# fabflash-mk-2-driver.net
KiCad netlist of a schematic drawn in EAGLE
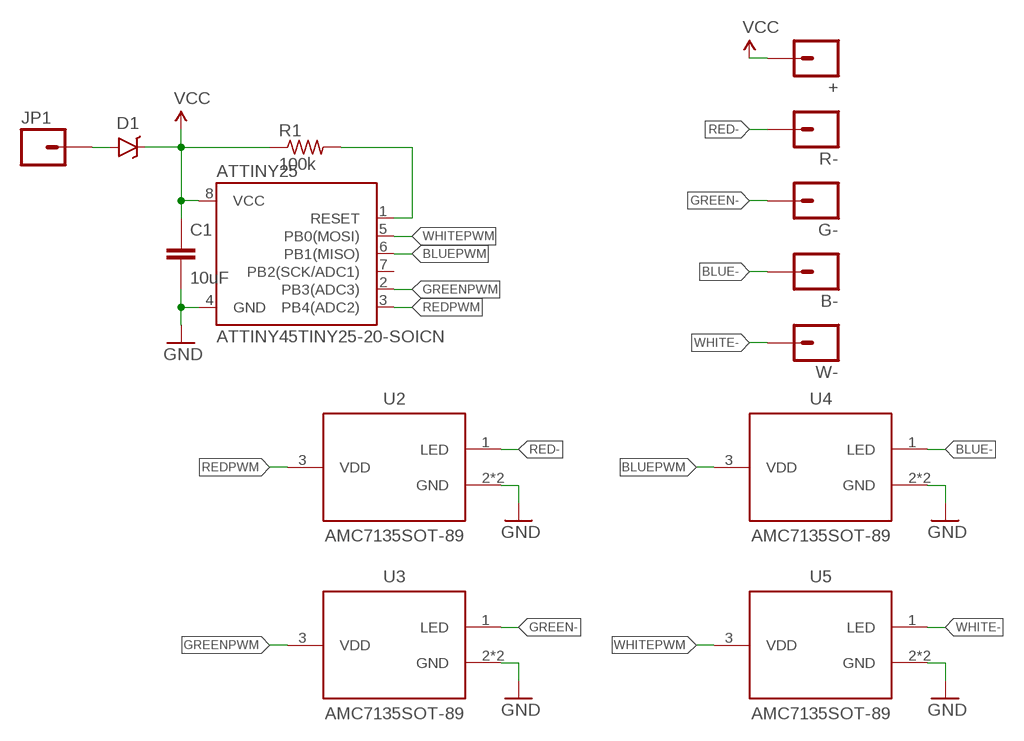
[diagram p0: schematic, sheet 1]

(export (version "E")
  (design (tool "Eeschema 10.0.6"))
  (components
    (comp (ref "+")
      (value "M01PTH-0.9MM")
      (footprint "eagle-import:1X01-0.9MM-NS")
      (libsource (lib "eagle-import") (part "M01PTH-0.9MM"))
    )
    (comp (ref "ATTINY25")
      (value "ATTINY45TINY25-20-SOICN")
      (footprint "eagle-import:SO08")
      (libsource (lib "eagle-import") (part "ATTINY45TINY25-20-SOICN"))
    )
    (comp (ref "B-")
      (value "M01PTH-0.9MM")
      (footprint "eagle-import:1X01-0.9MM-NS")
      (libsource (lib "eagle-import") (part "M01PTH-0.9MM"))
    )
    (comp (ref "C1")
      (value "10uF")
      (footprint "eagle-import:C0805")
      (libsource (lib "eagle-import") (part "CAPACITOR-CERAMICC0805"))
    )
    (comp (ref "D1")
      (value "MBRA140")
      (footprint "eagle-import:SMA-DIODE")
      (libsource (lib "eagle-import") (part "DIODE-SCHOTTKYMBRA140"))
    )
    (comp (ref "G-")
      (value "M01PTH-0.9MM")
      (footprint "eagle-import:1X01-0.9MM-NS")
      (libsource (lib "eagle-import") (part "M01PTH-0.9MM"))
    )
    (comp (ref "JP1")
      (value "M01NOT-A-VIA-NOPE")
      (footprint "eagle-import:1X01_NOSILK_NOSTOP")
      (libsource (lib "eagle-import") (part "M01NOT-A-VIA-NOPE"))
    )
    (comp (ref "R-")
      (value "M01PTH-0.9MM")
      (footprint "eagle-import:1X01-0.9MM-NS")
      (libsource (lib "eagle-import") (part "M01PTH-0.9MM"))
    )
    (comp (ref "R1")
      (value "100k")
      (footprint "eagle-import:R0805")
      (libsource (lib "eagle-import") (part "RESISTORR0805"))
    )
    (comp (ref "U2")
      (value "AMC7135SOT-89")
      (footprint "eagle-import:SOT89")
      (libsource (lib "eagle-import") (part "AMC7135SOT-89"))
    )
    (comp (ref "U3")
      (value "AMC7135SOT-89")
      (footprint "eagle-import:SOT89")
      (libsource (lib "eagle-import") (part "AMC7135SOT-89"))
    )
    (comp (ref "U4")
      (value "AMC7135SOT-89")
      (footprint "eagle-import:SOT89")
      (libsource (lib "eagle-import") (part "AMC7135SOT-89"))
    )
    (comp (ref "U5")
      (value "AMC7135SOT-89")
      (footprint "eagle-import:SOT89")
      (libsource (lib "eagle-import") (part "AMC7135SOT-89"))
    )
    (comp (ref "W-")
      (value "M01PTH-0.9MM")
      (footprint "eagle-import:1X01-0.9MM-NS")
      (libsource (lib "eagle-import") (part "M01PTH-0.9MM"))
    )
  )
  (nets
    (net (code "1") (name "BLUE-") (class "Default")
      (node (ref "B-") (pin "1") (pinfunction "1_1") (pintype "passive"))
      (node (ref "U4") (pin "1") (pinfunction "LED_1") (pintype "bidirectional"))
    )
    (net (code "2") (name "BLUEPWM") (class "Default")
      (node (ref "ATTINY25") (pin "6") (pinfunction "PB1(MISO)_6") (pintype "bidirectional"))
      (node (ref "U4") (pin "3") (pinfunction "VDD_3") (pintype "bidirectional"))
    )
    (net (code "3") (name "GND") (class "Default")
      (node (ref "ATTINY25") (pin "4") (pinfunction "GND_4") (pintype "bidirectional"))
      (node (ref "C1") (pin "2") (pinfunction "2_2") (pintype "passive"))
      (node (ref "U2") (pin "2") (pinfunction "GND_2") (pintype "bidirectional"))
      (node (ref "U2") (pin "4") (pinfunction "GND_4") (pintype "bidirectional"))
      (node (ref "U3") (pin "2") (pinfunction "GND_2") (pintype "bidirectional"))
      (node (ref "U3") (pin "4") (pinfunction "GND_4") (pintype "bidirectional"))
      (node (ref "U4") (pin "2") (pinfunction "GND_2") (pintype "bidirectional"))
      (node (ref "U4") (pin "4") (pinfunction "GND_4") (pintype "bidirectional"))
      (node (ref "U5") (pin "2") (pinfunction "GND_2") (pintype "bidirectional"))
      (node (ref "U5") (pin "4") (pinfunction "GND_4") (pintype "bidirectional"))
    )
    (net (code "4") (name "GREEN-") (class "Default")
      (node (ref "G-") (pin "1") (pinfunction "1_1") (pintype "passive"))
      (node (ref "U3") (pin "1") (pinfunction "LED_1") (pintype "bidirectional"))
    )
    (net (code "5") (name "GREENPWM") (class "Default")
      (node (ref "ATTINY25") (pin "2") (pinfunction "PB3(ADC3)_2") (pintype "bidirectional"))
      (node (ref "U3") (pin "3") (pinfunction "VDD_3") (pintype "bidirectional"))
    )
    (net (code "6") (name "Net-(ATTINY25-RESET)") (class "Default")
      (node (ref "ATTINY25") (pin "1") (pinfunction "RESET_1") (pintype "bidirectional"))
      (node (ref "R1") (pin "2") (pinfunction "2_2") (pintype "passive"))
    )
    (net (code "7") (name "Net-(JP1-1)") (class "Default")
      (node (ref "D1") (pin "A") (pinfunction "A_A") (pintype "passive"))
      (node (ref "JP1") (pin "P$1") (pinfunction "1_P$1") (pintype "passive"))
    )
    (net (code "8") (name "RED-") (class "Default")
      (node (ref "R-") (pin "1") (pinfunction "1_1") (pintype "passive"))
      (node (ref "U2") (pin "1") (pinfunction "LED_1") (pintype "bidirectional"))
    )
    (net (code "9") (name "REDPWM") (class "Default")
      (node (ref "ATTINY25") (pin "3") (pinfunction "PB4(ADC2)_3") (pintype "bidirectional"))
      (node (ref "U2") (pin "3") (pinfunction "VDD_3") (pintype "bidirectional"))
    )
    (net (code "10") (name "VCC") (class "Default")
      (node (ref "+") (pin "1") (pinfunction "1_1") (pintype "passive"))
      (node (ref "ATTINY25") (pin "8") (pinfunction "VCC_8") (pintype "bidirectional"))
      (node (ref "C1") (pin "1") (pinfunction "1_1") (pintype "passive"))
      (node (ref "D1") (pin "C") (pinfunction "C_C") (pintype "passive"))
      (node (ref "R1") (pin "1") (pinfunction "1_1") (pintype "passive"))
    )
    (net (code "11") (name "WHITE-") (class "Default")
      (node (ref "U5") (pin "1") (pinfunction "LED_1") (pintype "bidirectional"))
      (node (ref "W-") (pin "1") (pinfunction "1_1") (pintype "passive"))
    )
    (net (code "12") (name "WHITEPWM") (class "Default")
      (node (ref "ATTINY25") (pin "5") (pinfunction "PB0(MOSI)_5") (pintype "bidirectional"))
      (node (ref "U5") (pin "3") (pinfunction "VDD_3") (pintype "bidirectional"))
    )
    (net (code "13") (name "unconnected-(ATTINY25-PB2(SCK{slash}ADC1)-Pad7)") (class "Default")
      (node (ref "ATTINY25") (pin "7") (pinfunction "PB2(SCK/ADC1)_7") (pintype "bidirectional"))
    )
  )
)
